# HUZZAH32.net
KiCad netlist of a schematic drawn in Altium Designer
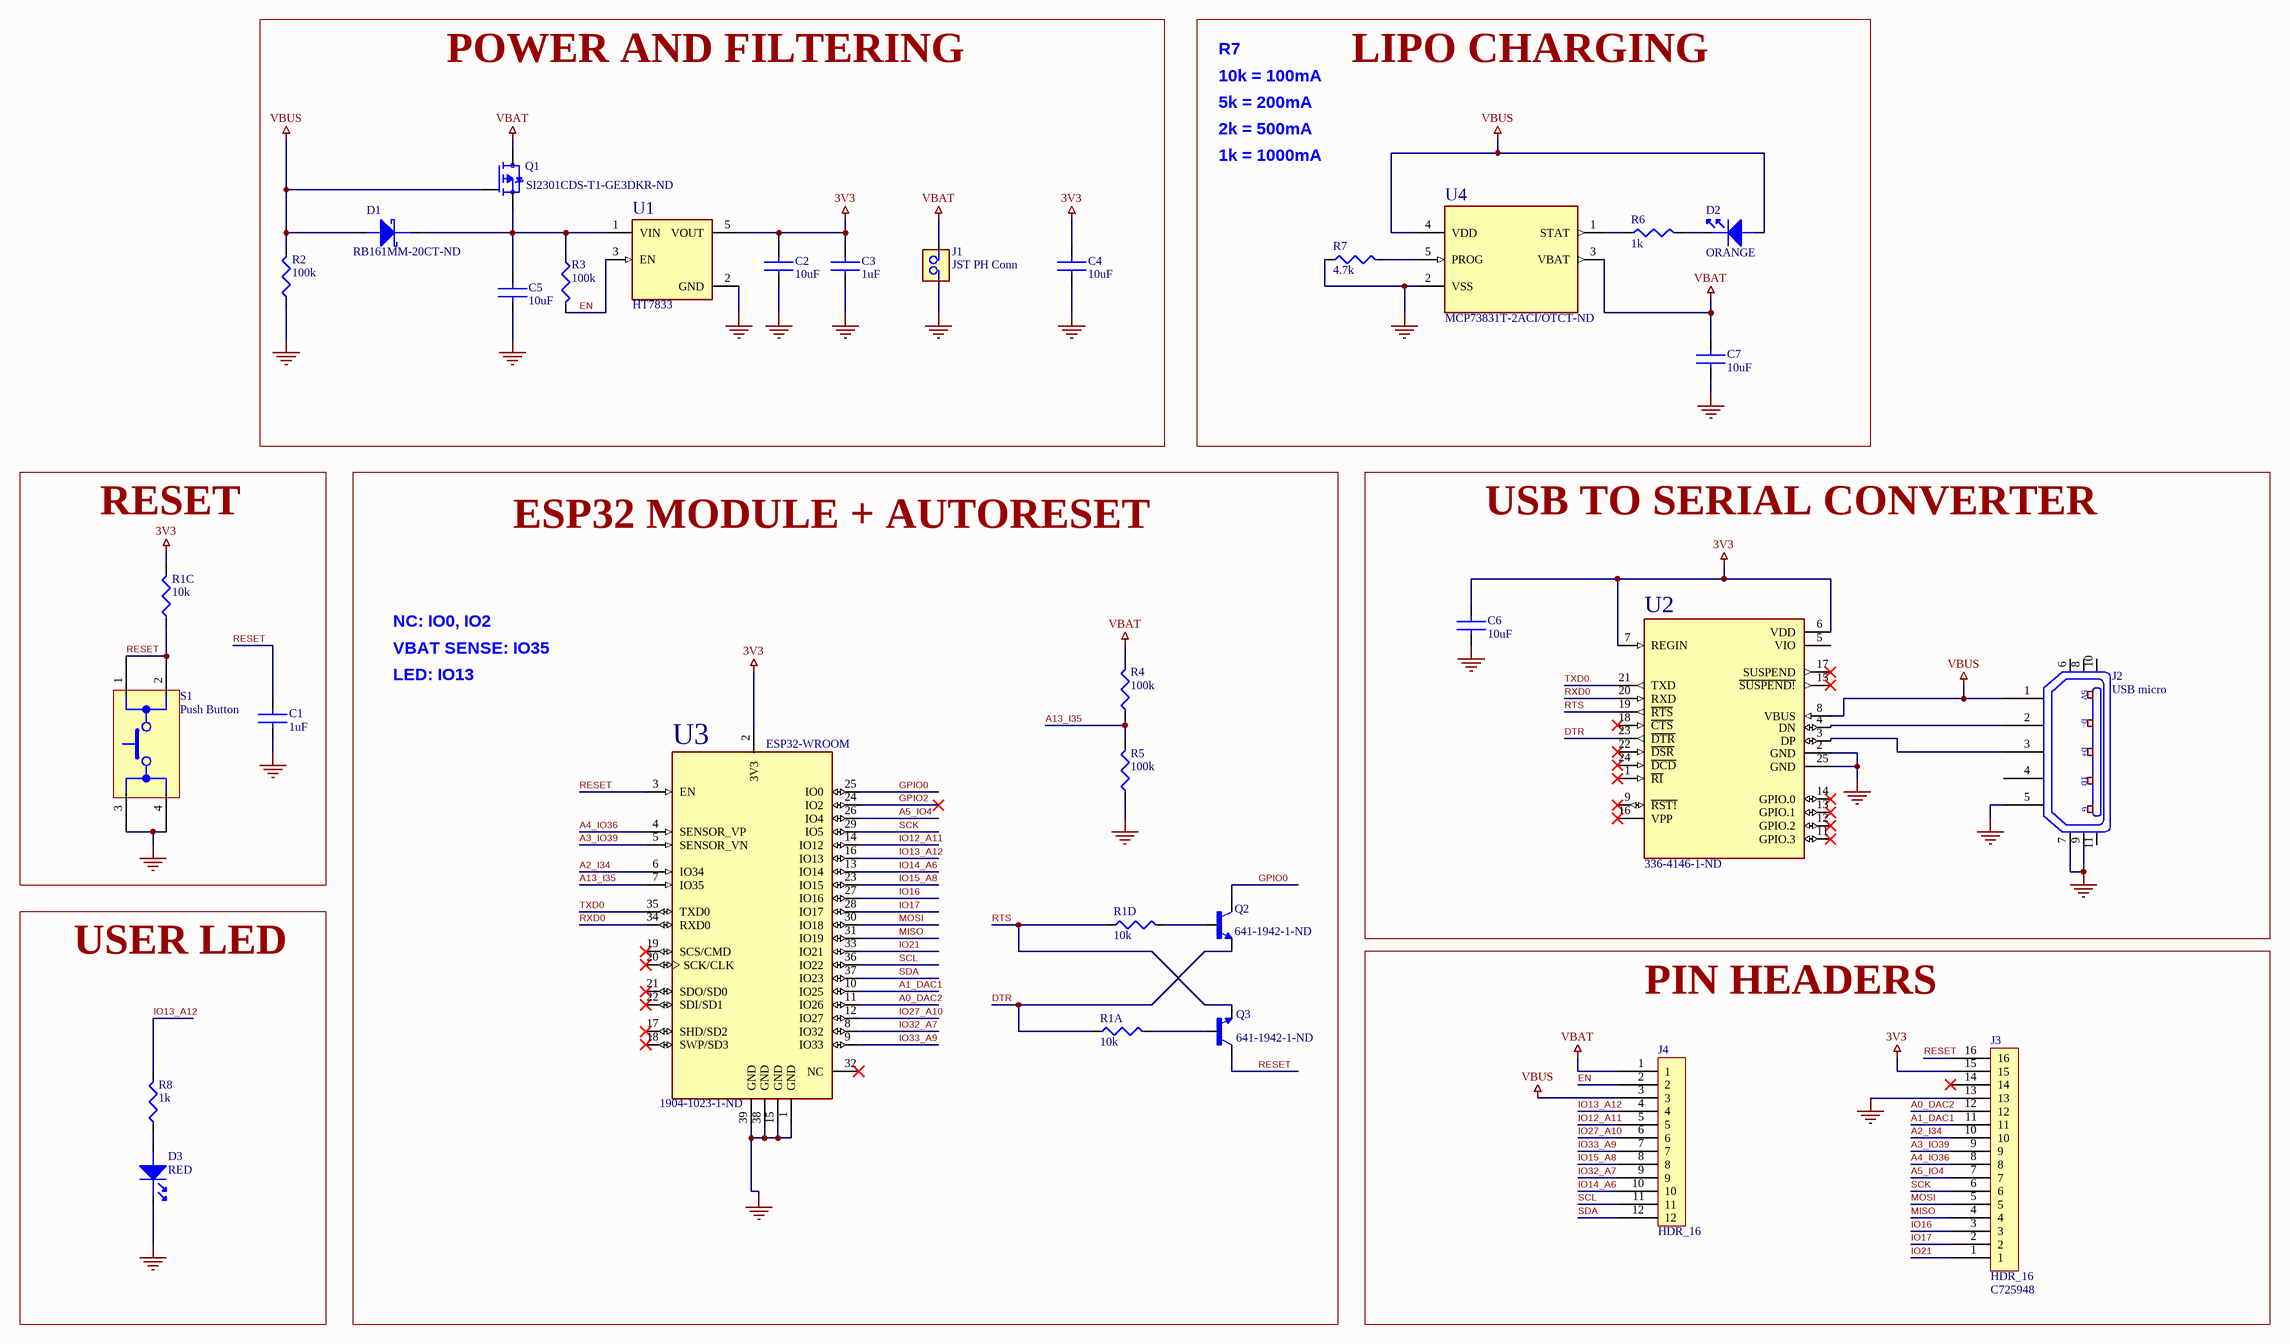
[diagram p0: HUZZAH32.SchDoc]

(export (version "E")
  (design (tool "Eeschema 10.0.6"))
  (components
    (comp (ref "C1")
      (value "1uF")
      (footprint "Ceramic_0805")
      (description "1uF 16V ±10% 0805 MLCC")
      (libsource (lib "HUZZAH32") (part "1276-1026-1-ND"))
    )
    (comp (ref "C2")
      (value "10uF")
      (footprint "Ceramic_0805")
      (description "1uF 16V ±10% 0805 MLCC")
      (libsource (lib "HUZZAH32") (part "1276-1096-1-ND"))
    )
    (comp (ref "C3")
      (value "1uF")
      (footprint "Ceramic_0805")
      (description "1uF 16V ±10% 0805 MLCC")
      (libsource (lib "HUZZAH32") (part "1276-1026-1-ND"))
    )
    (comp (ref "C4")
      (value "10uF")
      (footprint "Ceramic_0805")
      (description "1uF 16V ±10% 0805 MLCC")
      (libsource (lib "HUZZAH32") (part "1276-1096-1-ND"))
    )
    (comp (ref "C5")
      (value "10uF")
      (footprint "Ceramic_0805")
      (description "1uF 16V ±10% 0805 MLCC")
      (libsource (lib "HUZZAH32") (part "1276-1096-1-ND"))
    )
    (comp (ref "C6")
      (value "10uF")
      (footprint "Ceramic_0805")
      (description "1uF 16V ±10% 0805 MLCC")
      (libsource (lib "HUZZAH32") (part "1276-1096-1-ND"))
    )
    (comp (ref "C7")
      (value "10uF")
      (footprint "Ceramic_0805")
      (description "1uF 16V ±10% 0805 MLCC")
      (libsource (lib "HUZZAH32") (part "1276-1096-1-ND"))
    )
    (comp (ref "D1")
      (value "Schottky")
      (footprint "SOD-123F")
      (description "Diode Schottky 20 V 1A Surface Mount SOD-123FL")
      (fields (field (name "SUPPLIER PART NUMBER 2") "RB161MM-20CT-ND"))
      (libsource (lib "HUZZAH32") (part "RB161MM-20CT-ND"))
    )
    (comp (ref "D2")
      (value "ORANGE")
      (footprint "LED_0805")
      (description "LED ORANGE 20mA 2V 0805")
      (libsource (lib "HUZZAH32") (part "LED_ORANGE"))
    )
    (comp (ref "D3")
      (value "RED")
      (footprint "LED_0805")
      (description "LED RED 20mA 2V 0805")
      (libsource (lib "HUZZAH32") (part "LED_RED"))
    )
    (comp (ref "J1")
      (value "JST PH Conn")
      (footprint "JST_PH_CONN_F_SMD")
      (description "1x2 JST PH 2mm SMD Connector")
      (libsource (lib "HUZZAH32") (part "JST-PH"))
    )
    (comp (ref "J2")
      (value "USB micro")
      (footprint "USB_CONN")
      (libsource (lib "HUZZAH32") (part "USB micro"))
    )
    (comp (ref "J3")
      (value "HDR_16")
      (footprint "HDR_16")
      (description "HEADER male 1x16 2.54mm")
      (fields (field (name "SUPPLIER PART NUMBER 1") "C725948"))
      (libsource (lib "HUZZAH32") (part "HDR_16"))
    )
    (comp (ref "J4")
      (value "HDR_16")
      (footprint "HDR_12")
      (description "HEADER male 1x12 2.54mm")
      (libsource (lib "HUZZAH32") (part "HDR_12"))
    )
    (comp (ref "Q1")
      (value "P Channel MOSFET")
      (footprint "SOT23-3")
      (description "P Channel MOSFET 20V 3.1A 860mW 112mΩ@4.5V SOT-23-3")
      (fields (field (name "SUPPLIER PART NUMBER 2") "SI2301CDS-T1-GE3DKR-ND"))
      (libsource (lib "HUZZAH32") (part "SI2301CDS-T1-GE3DKR-ND"))
    )
    (comp (ref "Q2")
      (value "BJT")
      (footprint "SOT23-3")
      (description "BJT NPN 40 V 600 mA 300MHz 300 mW SOT-23-3")
      (fields (field (name "SUPPLIER PART NUMBER 2") "641-1942-1-ND"))
      (libsource (lib "") (part "MMBT2222A_1"))
    )
    (comp (ref "Q3")
      (value "BJT")
      (footprint "SOT23-3")
      (description "BJT NPN 40 V 600 mA 300MHz 300 mW SOT-23-3")
      (fields (field (name "SUPPLIER PART NUMBER 2") "641-1942-1-ND"))
      (libsource (lib "HUZZAH32") (part "MMBT2222A"))
    )
    (comp (ref "R1")
      (value "10k")
      (footprint "SMD_4_RES_ARRAY_1206")
      (description "4 Resistor Array 10kΩ ±5% 1/16W 1206")
      (libsource (lib "HUZZAH32") (part "EXB-38V104JV"))
    )
    (comp (ref "R2")
      (value "100k")
      (footprint "R_0603")
      (description "RES SMD 100kΩ 5% 1/10W 0603")
      (libsource (lib "HUZZAH32") (part "0603WAJ0104T5E"))
    )
    (comp (ref "R3")
      (value "100k")
      (footprint "R_0603")
      (description "RES SMD 100kΩ 5% 1/10W 0603")
      (libsource (lib "HUZZAH32") (part "0603WAJ0104T5E"))
    )
    (comp (ref "R4")
      (value "100k")
      (footprint "R_0603")
      (description "RES SMD 100kΩ 5% 1/10W 0603")
      (libsource (lib "HUZZAH32") (part "0603WAJ0104T5E"))
    )
    (comp (ref "R5")
      (value "100k")
      (footprint "R_0603")
      (description "RES SMD 100kΩ 5% 1/10W 0603")
      (libsource (lib "HUZZAH32") (part "0603WAJ0104T5E"))
    )
    (comp (ref "R6")
      (value "1k")
      (footprint "R_0603")
      (description "RES SMD 1kΩ 5% 1/10W 0603")
      (libsource (lib "HUZZAH32") (part "0603WAJ0102T5E"))
    )
    (comp (ref "R7")
      (value "4.7k")
      (footprint "R_0603")
      (description "RES SMD 4.7kΩ 1% 1/10W 0603")
      (libsource (lib "HUZZAH32") (part "0603WAF4701T5E"))
    )
    (comp (ref "R8")
      (value "1k")
      (footprint "R_0603")
      (description "RES SMD 1kΩ 5% 1/10W 0603")
      (libsource (lib "HUZZAH32") (part "0603WAJ0102T5E"))
    )
    (comp (ref "S1")
      (value "Push Button")
      (footprint "SW_PB_6643")
      (description "SPST tactile switch SMD 6x6x4.3mm")
      (libsource (lib "HUZZAH32") (part "GT-TC089B-H043-L1"))
    )
    (comp (ref "U1")
      (value "HT7833")
      (footprint "SOT23-5")
      (description "Linear Voltage Regulator IC Positive Fixed 3V3 Output 500mA 500mV@(500mA) SOT-23-5")
      (libsource (lib "HUZZAH32") (part "HT7833"))
    )
    (comp (ref "U2")
      (value "USB to UART converter")
      (footprint "QFN_24")
      (description "USB Bridge, USB to UART USB 2.0 UART Interface")
      (fields (field (name "SUPPLIER PART NUMBER 2") "336-4146-1-ND"))
      (libsource (lib "HUZZAH32") (part "336-4146-1-ND"))
    )
    (comp (ref "U3")
      (value "ESP32-WROOM")
      (footprint "ESP32_WROOM_module")
      (fields (field (name "SUPPLIER PART NUMBER 4") "1904-1023-1-ND"))
      (libsource (lib "HUZZAH32") (part "1904-1023-1-ND"))
    )
    (comp (ref "U4")
      (value "IC BATT Conctroller")
      (footprint "SOT23-5")
      (description "Charger IC Lithium Ion/Polymer SOT-23-5 4.2V 500mA")
      (fields (field (name "SUPPLIER PART NUMBER 2") "MCP73831T-2ACI/OTCT-ND"))
      (libsource (lib "HUZZAH32") (part "MCP73831T-2ACI/OTCT-ND"))
    )
  )
  (nets
    (net (code "1") (name "/A0_DAC2") (class "Default")
      (node (ref "J3") (pin "12") (pinfunction "12_12") (pintype "passive"))
      (node (ref "U3") (pin "11") (pinfunction "IO26_11") (pintype "bidirectional"))
    )
    (net (code "2") (name "/A1_DAC1") (class "Default")
      (node (ref "J3") (pin "11") (pinfunction "11_11") (pintype "passive"))
      (node (ref "U3") (pin "10") (pinfunction "IO25_10") (pintype "bidirectional"))
    )
    (net (code "3") (name "/A2_I34") (class "Default")
      (node (ref "J3") (pin "10") (pinfunction "10_10") (pintype "passive"))
      (node (ref "U3") (pin "6") (pinfunction "IO34_6") (pintype "input"))
    )
    (net (code "4") (name "/A3_IO39") (class "Default")
      (node (ref "J3") (pin "9") (pinfunction "9_9") (pintype "passive"))
      (node (ref "U3") (pin "5") (pinfunction "SENSOR_VN_5") (pintype "input"))
    )
    (net (code "5") (name "/A4_IO36") (class "Default")
      (node (ref "J3") (pin "8") (pinfunction "8_8") (pintype "passive"))
      (node (ref "U3") (pin "4") (pinfunction "SENSOR_VP_4") (pintype "input"))
    )
    (net (code "6") (name "/A5_IO4") (class "Default")
      (node (ref "J3") (pin "7") (pinfunction "7_7") (pintype "passive"))
      (node (ref "U3") (pin "26") (pinfunction "IO4_26") (pintype "bidirectional"))
    )
    (net (code "7") (name "/A13_I35") (class "Default")
      (node (ref "R4") (pin "1") (pinfunction "1_1") (pintype "passive"))
      (node (ref "R5") (pin "2") (pinfunction "2_2") (pintype "passive"))
      (node (ref "U3") (pin "7") (pinfunction "IO35_7") (pintype "input"))
    )
    (net (code "8") (name "/DTR") (class "Default")
      (node (ref "Q2") (pin "2") (pinfunction "E_2") (pintype "passive"))
      (node (ref "R1") (pin "2") (pinfunction "2_2") (pintype "passive"))
      (node (ref "U2") (pin "23") (pinfunction "~{DTR}_23") (pintype "output"))
    )
    (net (code "9") (name "/EN") (class "Default")
      (node (ref "J4") (pin "2") (pinfunction "2_2") (pintype "passive"))
      (node (ref "R3") (pin "2") (pinfunction "2_2") (pintype "passive"))
      (node (ref "U1") (pin "3") (pinfunction "EN_3") (pintype "input"))
    )
    (net (code "10") (name "/GPIO0") (class "Default")
      (node (ref "Q2") (pin "3") (pinfunction "C_3") (pintype "passive"))
      (node (ref "U3") (pin "25") (pinfunction "IO0_25") (pintype "bidirectional"))
    )
    (net (code "11") (name "/GPIO2") (class "Default")
      (node (ref "U3") (pin "24") (pinfunction "IO2_24") (pintype "bidirectional+no_connect"))
    )
    (net (code "12") (name "/IO12_A11") (class "Default")
      (node (ref "J4") (pin "5") (pinfunction "5_5") (pintype "passive"))
      (node (ref "U3") (pin "14") (pinfunction "IO12_14") (pintype "bidirectional"))
    )
    (net (code "13") (name "/IO13_A12") (class "Default")
      (node (ref "J4") (pin "4") (pinfunction "4_4") (pintype "passive"))
      (node (ref "R8") (pin "2") (pinfunction "2_2") (pintype "passive"))
      (node (ref "U3") (pin "16") (pinfunction "IO13_16") (pintype "bidirectional"))
    )
    (net (code "14") (name "/IO14_A6") (class "Default")
      (node (ref "J4") (pin "10") (pinfunction "10_10") (pintype "passive"))
      (node (ref "U3") (pin "13") (pinfunction "IO14_13") (pintype "bidirectional"))
    )
    (net (code "15") (name "/IO15_A8") (class "Default")
      (node (ref "J4") (pin "8") (pinfunction "8_8") (pintype "passive"))
      (node (ref "U3") (pin "23") (pinfunction "IO15_23") (pintype "bidirectional"))
    )
    (net (code "16") (name "/IO16") (class "Default")
      (node (ref "J3") (pin "3") (pinfunction "3_3") (pintype "passive"))
      (node (ref "U3") (pin "27") (pinfunction "IO16_27") (pintype "bidirectional"))
    )
    (net (code "17") (name "/IO17") (class "Default")
      (node (ref "J3") (pin "2") (pinfunction "2_2") (pintype "passive"))
      (node (ref "U3") (pin "28") (pinfunction "IO17_28") (pintype "bidirectional"))
    )
    (net (code "18") (name "/IO21") (class "Default")
      (node (ref "J3") (pin "1") (pinfunction "1_1") (pintype "passive"))
      (node (ref "U3") (pin "33") (pinfunction "IO21_33") (pintype "bidirectional"))
    )
    (net (code "19") (name "/IO27_A10") (class "Default")
      (node (ref "J4") (pin "6") (pinfunction "6_6") (pintype "passive"))
      (node (ref "U3") (pin "12") (pinfunction "IO27_12") (pintype "bidirectional"))
    )
    (net (code "20") (name "/IO32_A7") (class "Default")
      (node (ref "J4") (pin "9") (pinfunction "9_9") (pintype "passive"))
      (node (ref "U3") (pin "8") (pinfunction "IO32_8") (pintype "bidirectional"))
    )
    (net (code "21") (name "/IO33_A9") (class "Default")
      (node (ref "J4") (pin "7") (pinfunction "7_7") (pintype "passive"))
      (node (ref "U3") (pin "9") (pinfunction "IO33_9") (pintype "bidirectional"))
    )
    (net (code "22") (name "/MISO") (class "Default")
      (node (ref "J3") (pin "4") (pinfunction "4_4") (pintype "passive"))
      (node (ref "U3") (pin "31") (pinfunction "IO19_31") (pintype "bidirectional"))
    )
    (net (code "23") (name "/MOSI") (class "Default")
      (node (ref "J3") (pin "5") (pinfunction "5_5") (pintype "passive"))
      (node (ref "U3") (pin "30") (pinfunction "IO18_30") (pintype "bidirectional"))
    )
    (net (code "24") (name "/RESET") (class "Default")
      (node (ref "C1") (pin "2") (pinfunction "2_2") (pintype "passive"))
      (node (ref "J3") (pin "16") (pinfunction "16_16") (pintype "passive"))
      (node (ref "Q3") (pin "3") (pinfunction "C_3") (pintype "passive"))
      (node (ref "R1") (pin "6") (pinfunction "6_6") (pintype "passive"))
      (node (ref "S1") (pin "1") (pinfunction "1_1") (pintype "passive"))
      (node (ref "S1") (pin "2") (pinfunction "2_2") (pintype "passive"))
      (node (ref "U3") (pin "3") (pinfunction "EN_3") (pintype "input"))
    )
    (net (code "25") (name "/RTS") (class "Default")
      (node (ref "Q3") (pin "2") (pinfunction "E_2") (pintype "passive"))
      (node (ref "R1") (pin "8") (pinfunction "8_8") (pintype "passive"))
      (node (ref "U2") (pin "19") (pinfunction "~{RTS}_19") (pintype "output"))
    )
    (net (code "26") (name "/RXD0") (class "Default")
      (node (ref "U2") (pin "20") (pinfunction "RXD_20") (pintype "input"))
      (node (ref "U3") (pin "34") (pinfunction "RXD0_34") (pintype "bidirectional"))
    )
    (net (code "27") (name "/SCK") (class "Default")
      (node (ref "J3") (pin "6") (pinfunction "6_6") (pintype "passive"))
      (node (ref "U3") (pin "29") (pinfunction "IO5_29") (pintype "bidirectional"))
    )
    (net (code "28") (name "/SCL") (class "Default")
      (node (ref "J4") (pin "11") (pinfunction "11_11") (pintype "passive"))
      (node (ref "U3") (pin "36") (pinfunction "IO22_36") (pintype "bidirectional"))
    )
    (net (code "29") (name "/SDA") (class "Default")
      (node (ref "J4") (pin "12") (pinfunction "12_12") (pintype "passive"))
      (node (ref "U3") (pin "37") (pinfunction "IO23_37") (pintype "bidirectional"))
    )
    (net (code "30") (name "/TXD0") (class "Default")
      (node (ref "U2") (pin "21") (pinfunction "TXD_21") (pintype "output"))
      (node (ref "U3") (pin "35") (pinfunction "TXD0_35") (pintype "bidirectional"))
    )
    (net (code "31") (name "3V3") (class "Default")
      (node (ref "C2") (pin "2") (pinfunction "2_2") (pintype "passive"))
      (node (ref "C3") (pin "2") (pinfunction "2_2") (pintype "passive"))
      (node (ref "C4") (pin "2") (pinfunction "2_2") (pintype "passive"))
      (node (ref "C6") (pin "1") (pinfunction "1_1") (pintype "passive"))
      (node (ref "J3") (pin "15") (pinfunction "15_15") (pintype "passive"))
      (node (ref "R1") (pin "5") (pinfunction "5_5") (pintype "passive"))
      (node (ref "U1") (pin "5") (pinfunction "VOUT_5") (pintype "power_in"))
      (node (ref "U2") (pin "6") (pinfunction "VDD_6") (pintype "power_in"))
      (node (ref "U2") (pin "7") (pinfunction "REGIN_7") (pintype "input"))
      (node (ref "U3") (pin "2") (pinfunction "3V3_2") (pintype "power_in"))
    )
    (net (code "32") (name "GND") (class "Default")
      (node (ref "C1") (pin "1") (pinfunction "1_1") (pintype "passive"))
      (node (ref "C2") (pin "1") (pinfunction "1_1") (pintype "passive"))
      (node (ref "C3") (pin "1") (pinfunction "1_1") (pintype "passive"))
      (node (ref "C4") (pin "1") (pinfunction "1_1") (pintype "passive"))
      (node (ref "C5") (pin "1") (pinfunction "1_1") (pintype "passive"))
      (node (ref "C6") (pin "2") (pinfunction "2_2") (pintype "passive"))
      (node (ref "C7") (pin "1") (pinfunction "1_1") (pintype "passive"))
      (node (ref "D3") (pin "2") (pinfunction "C_2") (pintype "passive"))
      (node (ref "J1") (pin "1") (pinfunction "1_1") (pintype "passive"))
      (node (ref "J2") (pin "5") (pinfunction "GND_5") (pintype "passive"))
      (node (ref "J2") (pin "7") (pinfunction "7_7") (pintype "passive"))
      (node (ref "J2") (pin "9") (pinfunction "9_9") (pintype "passive"))
      (node (ref "J3") (pin "13") (pinfunction "13_13") (pintype "passive"))
      (node (ref "R2") (pin "1") (pinfunction "1_1") (pintype "passive"))
      (node (ref "R5") (pin "1") (pinfunction "1_1") (pintype "passive"))
      (node (ref "R7") (pin "1") (pinfunction "1_1") (pintype "passive"))
      (node (ref "S1") (pin "3") (pinfunction "3_3") (pintype "passive"))
      (node (ref "S1") (pin "4") (pinfunction "4_4") (pintype "passive"))
      (node (ref "U1") (pin "2") (pinfunction "GND_2") (pintype "power_in"))
      (node (ref "U2") (pin "2") (pinfunction "GND_2") (pintype "power_in"))
      (node (ref "U2") (pin "25") (pinfunction "GND_25") (pintype "power_in"))
      (node (ref "U3") (pin "1") (pinfunction "GND_1") (pintype "power_in"))
      (node (ref "U3") (pin "15") (pinfunction "GND_15") (pintype "power_in"))
      (node (ref "U3") (pin "38") (pinfunction "GND_38") (pintype "power_in"))
      (node (ref "U3") (pin "39") (pinfunction "GND_39") (pintype "power_in"))
      (node (ref "U4") (pin "2") (pinfunction "VSS_2") (pintype "power_in"))
    )
    (net (code "33") (name "Net-(D1-C)") (class "Default")
      (node (ref "C5") (pin "2") (pinfunction "2_2") (pintype "passive"))
      (node (ref "D1") (pin "2") (pinfunction "C_2") (pintype "passive"))
      (node (ref "Q1") (pin "2") (pinfunction "S_2") (pintype "passive"))
      (node (ref "R3") (pin "1") (pinfunction "1_1") (pintype "passive"))
      (node (ref "U1") (pin "1") (pinfunction "VIN_1") (pintype "power_in"))
    )
    (net (code "34") (name "Net-(D2-Cathode)") (class "Default")
      (node (ref "D2") (pin "1") (pinfunction "Cathode_1") (pintype "passive"))
      (node (ref "R6") (pin "2") (pinfunction "2_2") (pintype "passive"))
    )
    (net (code "35") (name "Net-(D3-A)") (class "Default")
      (node (ref "D3") (pin "1") (pinfunction "A_1") (pintype "passive"))
      (node (ref "R8") (pin "1") (pinfunction "1_1") (pintype "passive"))
    )
    (net (code "36") (name "Net-(J2-D+)") (class "Default")
      (node (ref "J2") (pin "3") (pinfunction "D+_3") (pintype "passive"))
      (node (ref "U2") (pin "3") (pinfunction "DP_3") (pintype "bidirectional"))
    )
    (net (code "37") (name "Net-(J2-D-)") (class "Default")
      (node (ref "J2") (pin "2") (pinfunction "D-_2") (pintype "passive"))
      (node (ref "U2") (pin "4") (pinfunction "DN_4") (pintype "bidirectional"))
    )
    (net (code "38") (name "Net-(Q2-B)") (class "Default")
      (node (ref "Q2") (pin "1") (pinfunction "B_1") (pintype "passive"))
      (node (ref "R1") (pin "7") (pinfunction "7_7") (pintype "passive"))
    )
    (net (code "39") (name "Net-(Q3-B)") (class "Default")
      (node (ref "Q3") (pin "1") (pinfunction "B_1") (pintype "passive"))
      (node (ref "R1") (pin "1") (pinfunction "1_1") (pintype "passive"))
    )
    (net (code "40") (name "Net-(U4-PROG)") (class "Default")
      (node (ref "R7") (pin "2") (pinfunction "2_2") (pintype "passive"))
      (node (ref "U4") (pin "5") (pinfunction "PROG_5") (pintype "input"))
    )
    (net (code "41") (name "Net-(U4-STAT)") (class "Default")
      (node (ref "R6") (pin "1") (pinfunction "1_1") (pintype "passive"))
      (node (ref "U4") (pin "1") (pinfunction "STAT_1") (pintype "output"))
    )
    (net (code "42") (name "VBAT") (class "Default")
      (node (ref "C7") (pin "2") (pinfunction "2_2") (pintype "passive"))
      (node (ref "J1") (pin "2") (pinfunction "2_2") (pintype "passive"))
      (node (ref "J4") (pin "1") (pinfunction "1_1") (pintype "passive"))
      (node (ref "Q1") (pin "3") (pinfunction "D_3") (pintype "passive"))
      (node (ref "R4") (pin "2") (pinfunction "2_2") (pintype "passive"))
      (node (ref "U4") (pin "3") (pinfunction "VBAT_3") (pintype "output"))
    )
    (net (code "43") (name "VBUS") (class "Default")
      (node (ref "D1") (pin "1") (pinfunction "A_1") (pintype "passive"))
      (node (ref "D2") (pin "2") (pinfunction "Anode_2") (pintype "passive"))
      (node (ref "J2") (pin "1") (pinfunction "VBUS_1") (pintype "passive"))
      (node (ref "J4") (pin "3") (pinfunction "3_3") (pintype "passive"))
      (node (ref "Q1") (pin "1") (pinfunction "G_1") (pintype "passive"))
      (node (ref "R2") (pin "2") (pinfunction "2_2") (pintype "passive"))
      (node (ref "U2") (pin "8") (pinfunction "VBUS_8") (pintype "input"))
      (node (ref "U4") (pin "4") (pinfunction "VDD_4") (pintype "power_in"))
    )
    (net (code "44") (name "unconnected-(J2-ID-Pad4)") (class "Default")
      (node (ref "J2") (pin "4") (pinfunction "ID_4") (pintype "passive"))
    )
    (net (code "45") (name "unconnected-(J2-Pad6)") (class "Default")
      (node (ref "J2") (pin "6") (pinfunction "6_6") (pintype "passive"))
    )
    (net (code "46") (name "unconnected-(J2-Pad8)") (class "Default")
      (node (ref "J2") (pin "8") (pinfunction "8_8") (pintype "passive"))
    )
    (net (code "47") (name "unconnected-(J2-Pad10)") (class "Default")
      (node (ref "J2") (pin "10") (pinfunction "10_10") (pintype "passive"))
    )
    (net (code "48") (name "unconnected-(J2-Pad11)") (class "Default")
      (node (ref "J2") (pin "11") (pinfunction "11_11") (pintype "passive"))
    )
    (net (code "49") (name "unconnected-(J3-Pad14)") (class "Default")
      (node (ref "J3") (pin "14") (pinfunction "14_14") (pintype "passive"))
    )
    (net (code "50") (name "unconnected-(U2-GPIO.0-Pad14)") (class "Default")
      (node (ref "U2") (pin "14") (pinfunction "GPIO.0_14") (pintype "bidirectional+no_connect"))
    )
    (net (code "51") (name "unconnected-(U2-GPIO.1-Pad13)") (class "Default")
      (node (ref "U2") (pin "13") (pinfunction "GPIO.1_13") (pintype "bidirectional+no_connect"))
    )
    (net (code "52") (name "unconnected-(U2-GPIO.2-Pad12)") (class "Default")
      (node (ref "U2") (pin "12") (pinfunction "GPIO.2_12") (pintype "bidirectional+no_connect"))
    )
    (net (code "53") (name "unconnected-(U2-GPIO.3-Pad11)") (class "Default")
      (node (ref "U2") (pin "11") (pinfunction "GPIO.3_11") (pintype "bidirectional+no_connect"))
    )
    (net (code "54") (name "unconnected-(U2-SUSPEND-Pad17)") (class "Default")
      (node (ref "U2") (pin "17") (pinfunction "SUSPEND_17") (pintype "output+no_connect"))
    )
    (net (code "55") (name "unconnected-(U2-VIO-Pad5)") (class "Default")
      (node (ref "U2") (pin "5") (pinfunction "VIO_5") (pintype "power_in"))
    )
    (net (code "56") (name "unconnected-(U2-VPP-Pad16)") (class "Default")
      (node (ref "U2") (pin "16") (pinfunction "VPP_16") (pintype "passive+no_connect"))
    )
    (net (code "57") (name "unconnected-(U2-~{CTS}-Pad18)") (class "Default")
      (node (ref "U2") (pin "18") (pinfunction "~{CTS}_18") (pintype "input+no_connect"))
    )
    (net (code "58") (name "unconnected-(U2-~{DCD}-Pad24)") (class "Default")
      (node (ref "U2") (pin "24") (pinfunction "~{DCD}_24") (pintype "input+no_connect"))
    )
    (net (code "59") (name "unconnected-(U2-~{DSR}-Pad22)") (class "Default")
      (node (ref "U2") (pin "22") (pinfunction "~{DSR}_22") (pintype "input+no_connect"))
    )
    (net (code "60") (name "unconnected-(U2-~{RI}-Pad1)") (class "Default")
      (node (ref "U2") (pin "1") (pinfunction "~{RI}_1") (pintype "input+no_connect"))
    )
    (net (code "61") (name "unconnected-(U2-~{RST!}-Pad9)") (class "Default")
      (node (ref "U2") (pin "9") (pinfunction "~{RST!}_9") (pintype "bidirectional+no_connect"))
    )
    (net (code "62") (name "unconnected-(U2-~{SUSPEND!}-Pad15)") (class "Default")
      (node (ref "U2") (pin "15") (pinfunction "~{SUSPEND!}_15") (pintype "output+no_connect"))
    )
    (net (code "63") (name "unconnected-(U3-NC-Pad32)") (class "Default")
      (node (ref "U3") (pin "32") (pinfunction "NC_32") (pintype "passive+no_connect"))
    )
    (net (code "64") (name "unconnected-(U3-SCK{slash}CLK-Pad20)") (class "Default")
      (node (ref "U3") (pin "20") (pinfunction "SCK/CLK_20") (pintype "bidirectional+no_connect"))
    )
    (net (code "65") (name "unconnected-(U3-SCS{slash}CMD-Pad19)") (class "Default")
      (node (ref "U3") (pin "19") (pinfunction "SCS/CMD_19") (pintype "bidirectional+no_connect"))
    )
    (net (code "66") (name "unconnected-(U3-SDI{slash}SD1-Pad22)") (class "Default")
      (node (ref "U3") (pin "22") (pinfunction "SDI/SD1_22") (pintype "bidirectional+no_connect"))
    )
    (net (code "67") (name "unconnected-(U3-SDO{slash}SD0-Pad21)") (class "Default")
      (node (ref "U3") (pin "21") (pinfunction "SDO/SD0_21") (pintype "bidirectional+no_connect"))
    )
    (net (code "68") (name "unconnected-(U3-SHD{slash}SD2-Pad17)") (class "Default")
      (node (ref "U3") (pin "17") (pinfunction "SHD/SD2_17") (pintype "bidirectional+no_connect"))
    )
    (net (code "69") (name "unconnected-(U3-SWP{slash}SD3-Pad18)") (class "Default")
      (node (ref "U3") (pin "18") (pinfunction "SWP/SD3_18") (pintype "bidirectional+no_connect"))
    )
  )
)
